# HYDRA_V2_1_POWER.net
KiCad netlist of a schematic drawn in Altium Designer
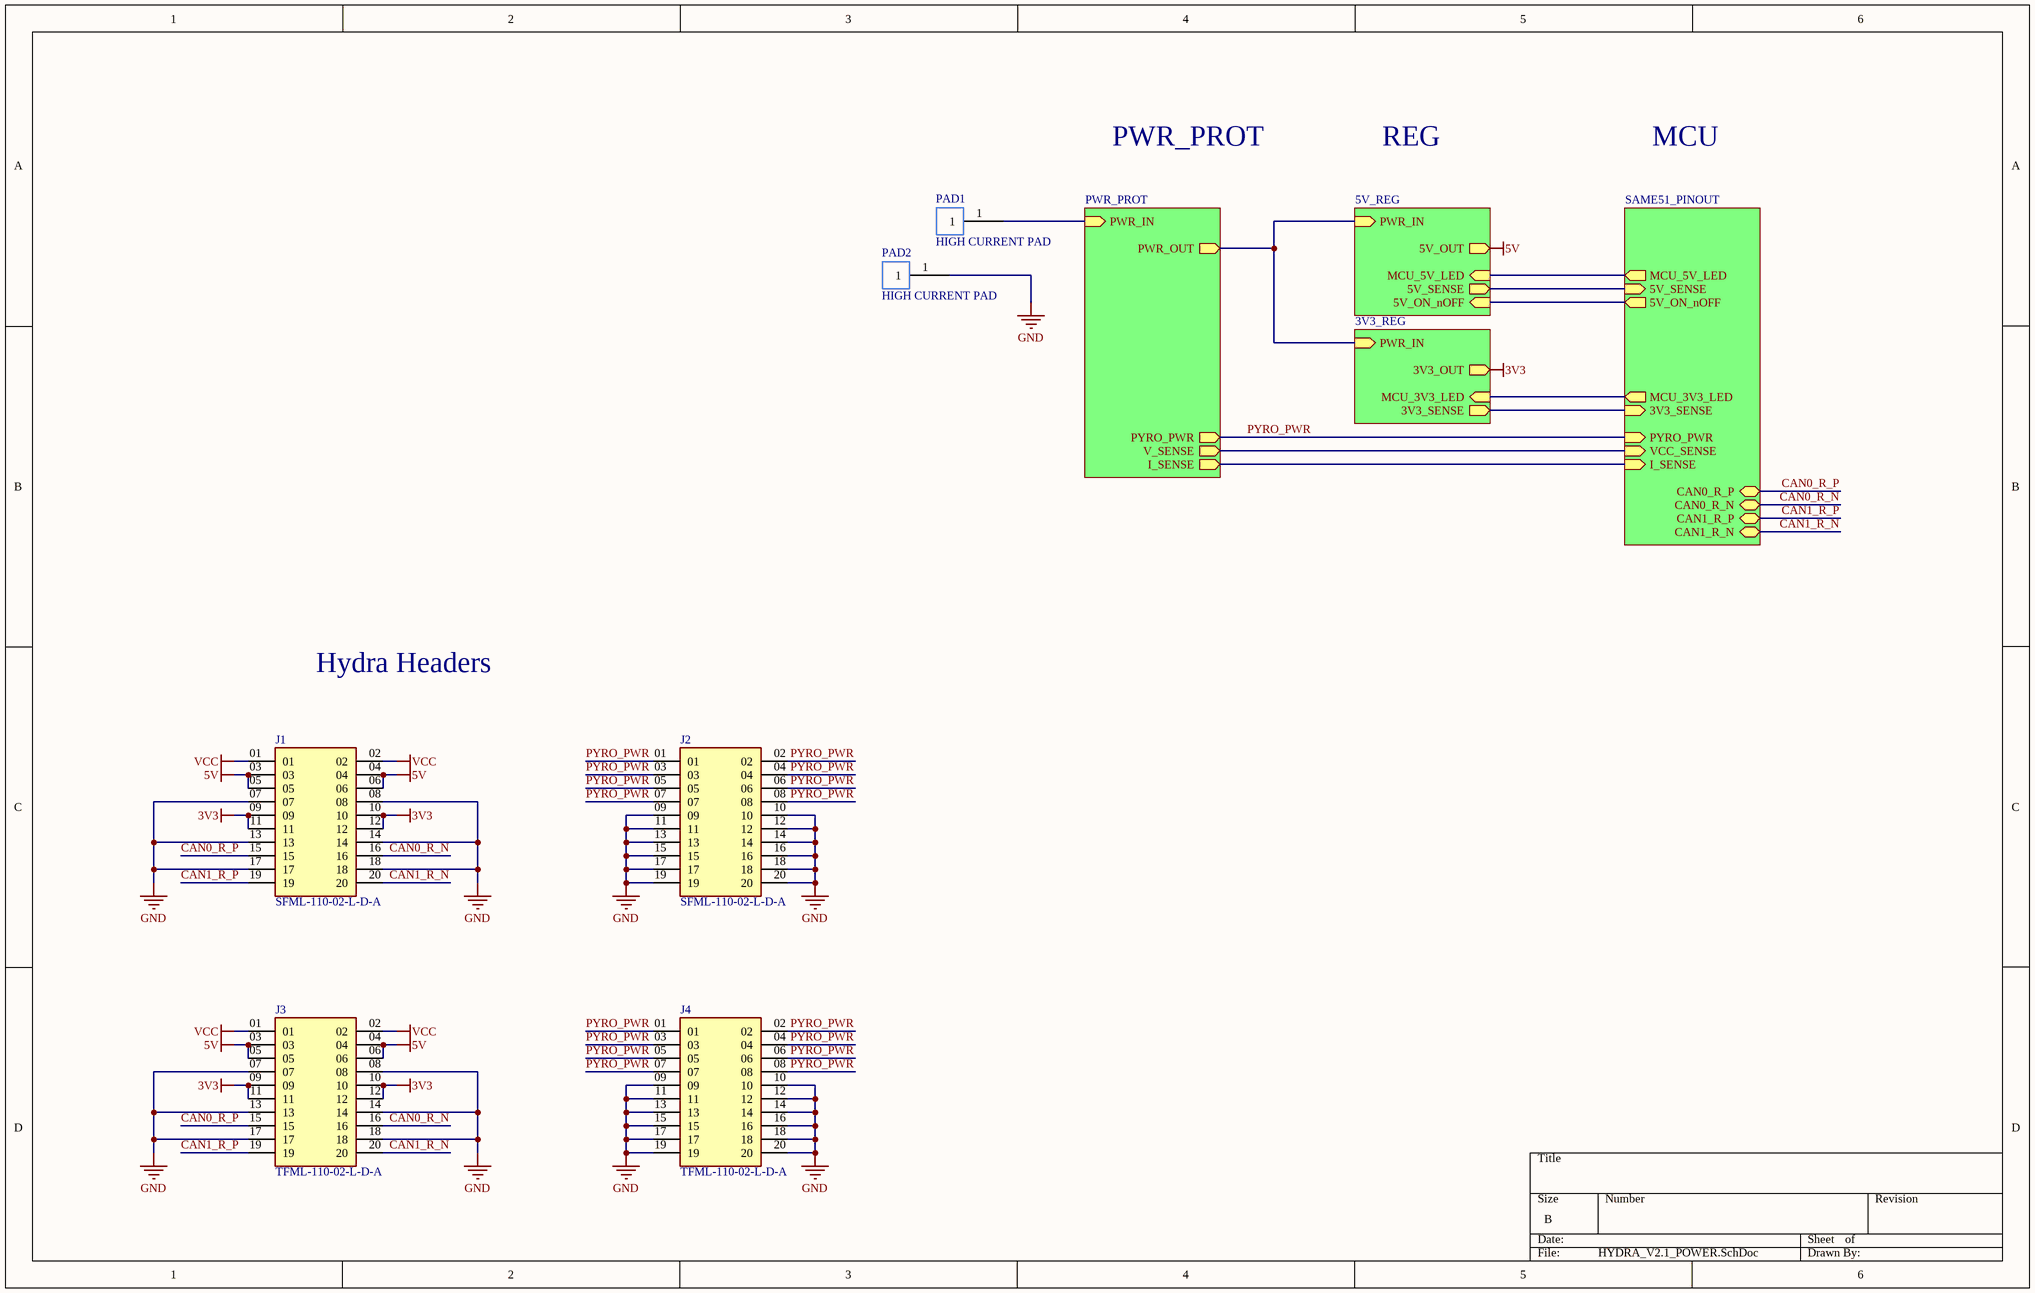
[diagram p0: HYDRA_V2.1_POWER.SchDoc]

(export (version "E")
  (design (tool "Eeschema 10.0.6"))
  (components
    (comp (ref "J1")
      (value "SFML-110-02-L-D-A")
      (footprint "SFML-110-02-L-D-A-Footprint-1")
      (description "Headers & Wire Housings .050 Tiger Eye High-Reliability Locking Socket Strip")
      (libsource (lib "uORocketry Hardware") (part "SFML-110-02-L-D-A"))
    )
    (comp (ref "J2")
      (value "SFML-110-02-L-D-A")
      (footprint "SFML-110-02-L-D-A-Footprint-1")
      (description "Headers & Wire Housings .050 Tiger Eye High-Reliability Locking Socket Strip")
      (libsource (lib "uORocketry Hardware") (part "SFML-110-02-L-D-A"))
    )
    (comp (ref "J3")
      (value "TFML-110-02-L-D-A")
      (footprint "TFML-110-02-L-D-A-Footprint-1")
      (description "Conn Shrouded Header (4 Sides) HDR 20 POS 1.27mm Solder ST Top Entry SMD TIGER EYE™ Tube")
      (libsource (lib "uORocketry Hardware") (part "TFML-110-02-L-D-A"))
    )
    (comp (ref "J4")
      (value "TFML-110-02-L-D-A")
      (footprint "TFML-110-02-L-D-A-Footprint-1")
      (description "Conn Shrouded Header (4 Sides) HDR 20 POS 1.27mm Solder ST Top Entry SMD TIGER EYE™ Tube")
      (libsource (lib "uORocketry Hardware") (part "TFML-110-02-L-D-A"))
    )
    (comp (ref "PAD1")
      (value "HIGH CURRENT PAD")
      (footprint "HIGH CURRENT PAD-Footprint-1")
      (description "Via stitched high current pad")
      (libsource (lib "uORocketry Hardware") (part "HIGH CURRENT PAD"))
    )
    (comp (ref "PAD2")
      (value "HIGH CURRENT PAD")
      (footprint "HIGH CURRENT PAD-Footprint-1")
      (description "Via stitched high current pad")
      (libsource (lib "uORocketry Hardware") (part "HIGH CURRENT PAD"))
    )
  )
  (nets
    (net (code "4") (name "/CAN0_R_N") (class "Default")
      (node (ref "J1") (pin "16") (pinfunction "16_16") (pintype "passive"))
      (node (ref "J3") (pin "16") (pinfunction "16_16") (pintype "passive"))
    )
    (net (code "5") (name "/CAN0_R_P") (class "Default")
      (node (ref "J1") (pin "15") (pinfunction "15_15") (pintype "passive"))
      (node (ref "J3") (pin "15") (pinfunction "15_15") (pintype "passive"))
    )
    (net (code "6") (name "/CAN1_R_N") (class "Default")
      (node (ref "J1") (pin "20") (pinfunction "20_20") (pintype "passive"))
      (node (ref "J3") (pin "20") (pinfunction "20_20") (pintype "passive"))
    )
    (net (code "7") (name "/CAN1_R_P") (class "Default")
      (node (ref "J1") (pin "19") (pinfunction "19_19") (pintype "passive"))
      (node (ref "J3") (pin "19") (pinfunction "19_19") (pintype "passive"))
    )
    (net (code "11") (name "/PWR_IN") (class "Default")
      (node (ref "PAD1") (pin "1") (pinfunction "1_1") (pintype "passive"))
    )
    (net (code "13") (name "/PYRO_PWR") (class "Default")
      (node (ref "J2") (pin "01") (pinfunction "01_01") (pintype "passive"))
      (node (ref "J2") (pin "02") (pinfunction "02_02") (pintype "passive"))
      (node (ref "J2") (pin "03") (pinfunction "03_03") (pintype "passive"))
      (node (ref "J2") (pin "04") (pinfunction "04_04") (pintype "passive"))
      (node (ref "J2") (pin "05") (pinfunction "05_05") (pintype "passive"))
      (node (ref "J2") (pin "06") (pinfunction "06_06") (pintype "passive"))
      (node (ref "J2") (pin "07") (pinfunction "07_07") (pintype "passive"))
      (node (ref "J2") (pin "08") (pinfunction "08_08") (pintype "passive"))
      (node (ref "J4") (pin "01") (pinfunction "01_01") (pintype "passive"))
      (node (ref "J4") (pin "02") (pinfunction "02_02") (pintype "passive"))
      (node (ref "J4") (pin "03") (pinfunction "03_03") (pintype "passive"))
      (node (ref "J4") (pin "04") (pinfunction "04_04") (pintype "passive"))
      (node (ref "J4") (pin "05") (pinfunction "05_05") (pintype "passive"))
      (node (ref "J4") (pin "06") (pinfunction "06_06") (pintype "passive"))
      (node (ref "J4") (pin "07") (pinfunction "07_07") (pintype "passive"))
      (node (ref "J4") (pin "08") (pinfunction "08_08") (pintype "passive"))
    )
    (net (code "15") (name "3V3") (class "Default")
      (node (ref "J1") (pin "09") (pinfunction "09_09") (pintype "passive"))
      (node (ref "J1") (pin "10") (pinfunction "10_10") (pintype "passive"))
      (node (ref "J1") (pin "11") (pinfunction "11_11") (pintype "passive"))
      (node (ref "J1") (pin "12") (pinfunction "12_12") (pintype "passive"))
      (node (ref "J3") (pin "09") (pinfunction "09_09") (pintype "passive"))
      (node (ref "J3") (pin "10") (pinfunction "10_10") (pintype "passive"))
      (node (ref "J3") (pin "11") (pinfunction "11_11") (pintype "passive"))
      (node (ref "J3") (pin "12") (pinfunction "12_12") (pintype "passive"))
    )
    (net (code "16") (name "5V") (class "Default")
      (node (ref "J1") (pin "03") (pinfunction "03_03") (pintype "passive"))
      (node (ref "J1") (pin "04") (pinfunction "04_04") (pintype "passive"))
      (node (ref "J1") (pin "05") (pinfunction "05_05") (pintype "passive"))
      (node (ref "J1") (pin "06") (pinfunction "06_06") (pintype "passive"))
      (node (ref "J3") (pin "03") (pinfunction "03_03") (pintype "passive"))
      (node (ref "J3") (pin "04") (pinfunction "04_04") (pintype "passive"))
      (node (ref "J3") (pin "05") (pinfunction "05_05") (pintype "passive"))
      (node (ref "J3") (pin "06") (pinfunction "06_06") (pintype "passive"))
    )
    (net (code "17") (name "GND") (class "Default")
      (node (ref "J1") (pin "07") (pinfunction "07_07") (pintype "passive"))
      (node (ref "J1") (pin "08") (pinfunction "08_08") (pintype "passive"))
      (node (ref "J1") (pin "13") (pinfunction "13_13") (pintype "passive"))
      (node (ref "J1") (pin "14") (pinfunction "14_14") (pintype "passive"))
      (node (ref "J1") (pin "17") (pinfunction "17_17") (pintype "passive"))
      (node (ref "J1") (pin "18") (pinfunction "18_18") (pintype "passive"))
      (node (ref "J2") (pin "09") (pinfunction "09_09") (pintype "passive"))
      (node (ref "J2") (pin "10") (pinfunction "10_10") (pintype "passive"))
      (node (ref "J2") (pin "11") (pinfunction "11_11") (pintype "passive"))
      (node (ref "J2") (pin "12") (pinfunction "12_12") (pintype "passive"))
      (node (ref "J2") (pin "13") (pinfunction "13_13") (pintype "passive"))
      (node (ref "J2") (pin "14") (pinfunction "14_14") (pintype "passive"))
      (node (ref "J2") (pin "15") (pinfunction "15_15") (pintype "passive"))
      (node (ref "J2") (pin "16") (pinfunction "16_16") (pintype "passive"))
      (node (ref "J2") (pin "17") (pinfunction "17_17") (pintype "passive"))
      (node (ref "J2") (pin "18") (pinfunction "18_18") (pintype "passive"))
      (node (ref "J2") (pin "19") (pinfunction "19_19") (pintype "passive"))
      (node (ref "J2") (pin "20") (pinfunction "20_20") (pintype "passive"))
      (node (ref "J3") (pin "07") (pinfunction "07_07") (pintype "passive"))
      (node (ref "J3") (pin "08") (pinfunction "08_08") (pintype "passive"))
      (node (ref "J3") (pin "13") (pinfunction "13_13") (pintype "passive"))
      (node (ref "J3") (pin "14") (pinfunction "14_14") (pintype "passive"))
      (node (ref "J3") (pin "17") (pinfunction "17_17") (pintype "passive"))
      (node (ref "J3") (pin "18") (pinfunction "18_18") (pintype "passive"))
      (node (ref "J4") (pin "09") (pinfunction "09_09") (pintype "passive"))
      (node (ref "J4") (pin "10") (pinfunction "10_10") (pintype "passive"))
      (node (ref "J4") (pin "11") (pinfunction "11_11") (pintype "passive"))
      (node (ref "J4") (pin "12") (pinfunction "12_12") (pintype "passive"))
      (node (ref "J4") (pin "13") (pinfunction "13_13") (pintype "passive"))
      (node (ref "J4") (pin "14") (pinfunction "14_14") (pintype "passive"))
      (node (ref "J4") (pin "15") (pinfunction "15_15") (pintype "passive"))
      (node (ref "J4") (pin "16") (pinfunction "16_16") (pintype "passive"))
      (node (ref "J4") (pin "17") (pinfunction "17_17") (pintype "passive"))
      (node (ref "J4") (pin "18") (pinfunction "18_18") (pintype "passive"))
      (node (ref "J4") (pin "19") (pinfunction "19_19") (pintype "passive"))
      (node (ref "J4") (pin "20") (pinfunction "20_20") (pintype "passive"))
      (node (ref "PAD2") (pin "1") (pinfunction "1_1") (pintype "passive"))
    )
    (net (code "18") (name "VCC") (class "Default")
      (node (ref "J1") (pin "01") (pinfunction "01_01") (pintype "passive"))
      (node (ref "J1") (pin "02") (pinfunction "02_02") (pintype "passive"))
      (node (ref "J3") (pin "01") (pinfunction "01_01") (pintype "passive"))
      (node (ref "J3") (pin "02") (pinfunction "02_02") (pintype "passive"))
    )
  )
)
